# lizard-ttl-dLatch.net
KiCad netlist of a schematic drawn in EAGLE
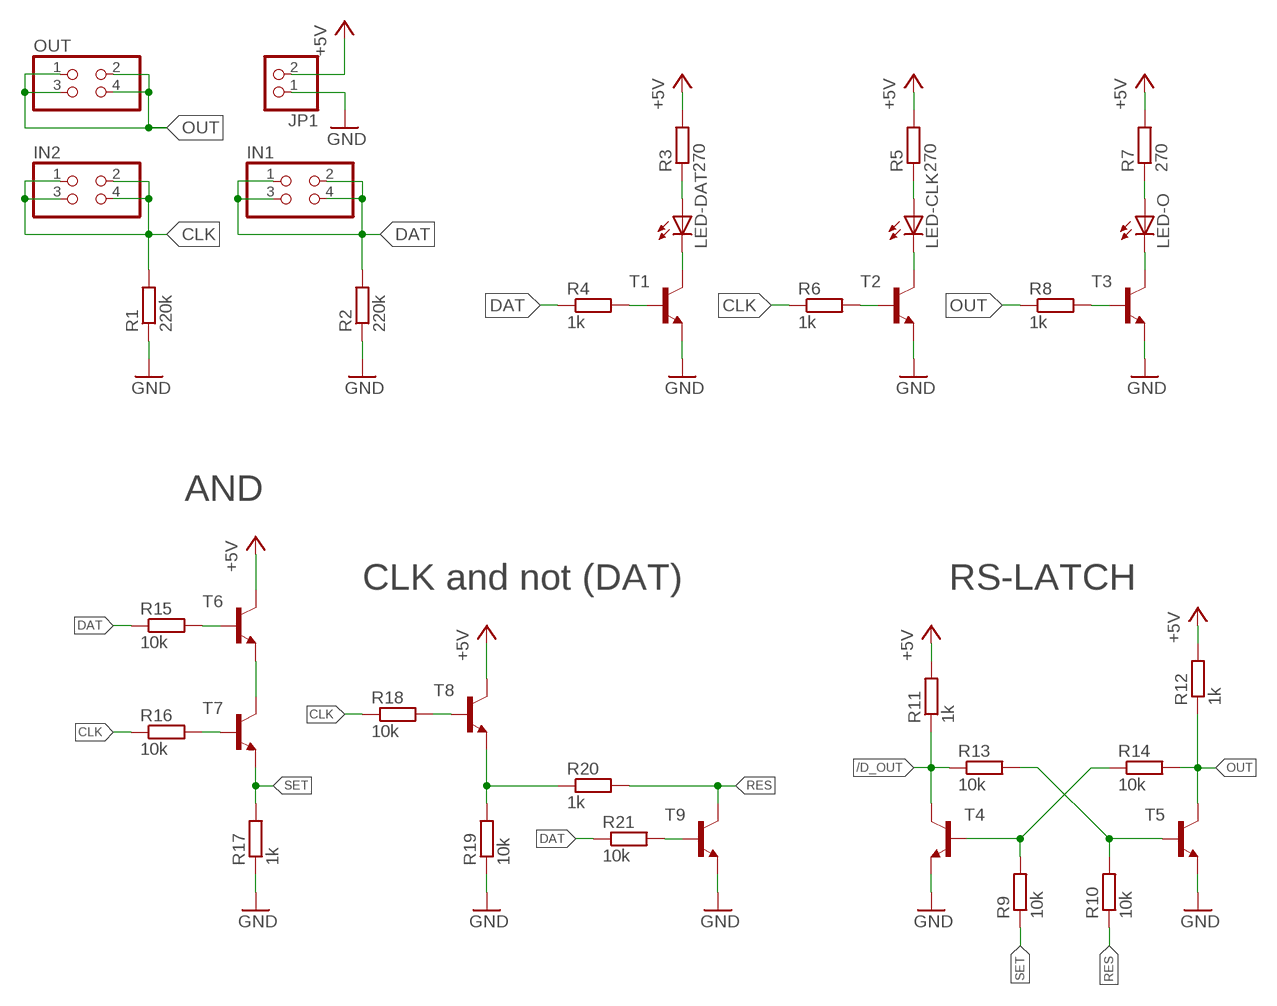
[diagram p0: schematic, sheet 1]

(export (version "E")
  (design (tool "Eeschema 10.0.6"))
  (components
    (comp (ref "IN1")
      (value "PINHD-2X2/EDGE")
      (footprint "eagle-import:2X02_EDGE")
      (libsource (lib "eagle-import") (part "PINHD-2X2/EDGE"))
    )
    (comp (ref "IN2")
      (value "PINHD-2X2/EDGE")
      (footprint "eagle-import:2X02_EDGE")
      (libsource (lib "eagle-import") (part "PINHD-2X2/EDGE"))
    )
    (comp (ref "JP1")
      (value "PINHD-1X2")
      (footprint "eagle-import:1X02")
      (libsource (lib "eagle-import") (part "PINHD-1X2"))
    )
    (comp (ref "LED-CLK")
      (value "LEDCHIPLED_0603")
      (footprint "eagle-import:CHIPLED_0603")
      (libsource (lib "eagle-import") (part "LEDCHIPLED_0603"))
    )
    (comp (ref "LED-DAT")
      (value "LEDCHIPLED_0603")
      (footprint "eagle-import:CHIPLED_0603")
      (libsource (lib "eagle-import") (part "LEDCHIPLED_0603"))
    )
    (comp (ref "LED-O")
      (value "LEDCHIPLED_0603")
      (footprint "eagle-import:CHIPLED_0603")
      (libsource (lib "eagle-import") (part "LEDCHIPLED_0603"))
    )
    (comp (ref "OUT")
      (value "PINHD-2X2/EDGE")
      (footprint "eagle-import:2X02_EDGE")
      (libsource (lib "eagle-import") (part "PINHD-2X2/EDGE"))
    )
    (comp (ref "R1")
      (value "220k")
      (footprint "eagle-import:R0603")
      (libsource (lib "eagle-import") (part "R-EU_R0603"))
    )
    (comp (ref "R2")
      (value "220k")
      (footprint "eagle-import:R0603")
      (libsource (lib "eagle-import") (part "R-EU_R0603"))
    )
    (comp (ref "R3")
      (value "270")
      (footprint "eagle-import:R0603")
      (libsource (lib "eagle-import") (part "R-EU_R0603"))
    )
    (comp (ref "R4")
      (value "1k")
      (footprint "eagle-import:R0603")
      (libsource (lib "eagle-import") (part "R-EU_R0603"))
    )
    (comp (ref "R5")
      (value "270")
      (footprint "eagle-import:R0603")
      (libsource (lib "eagle-import") (part "R-EU_R0603"))
    )
    (comp (ref "R6")
      (value "1k")
      (footprint "eagle-import:R0603")
      (libsource (lib "eagle-import") (part "R-EU_R0603"))
    )
    (comp (ref "R7")
      (value "270")
      (footprint "eagle-import:R0603")
      (libsource (lib "eagle-import") (part "R-EU_R0603"))
    )
    (comp (ref "R8")
      (value "1k")
      (footprint "eagle-import:R0603")
      (libsource (lib "eagle-import") (part "R-EU_R0603"))
    )
    (comp (ref "R9")
      (value "10k")
      (footprint "eagle-import:R0603")
      (libsource (lib "eagle-import") (part "R-EU_R0603"))
    )
    (comp (ref "R10")
      (value "10k")
      (footprint "eagle-import:R0603")
      (libsource (lib "eagle-import") (part "R-EU_R0603"))
    )
    (comp (ref "R11")
      (value "1k")
      (footprint "eagle-import:R0603")
      (libsource (lib "eagle-import") (part "R-EU_R0603"))
    )
    (comp (ref "R12")
      (value "1k")
      (footprint "eagle-import:R0603")
      (libsource (lib "eagle-import") (part "R-EU_R0603"))
    )
    (comp (ref "R13")
      (value "10k")
      (footprint "eagle-import:R0603")
      (libsource (lib "eagle-import") (part "R-EU_R0603"))
    )
    (comp (ref "R14")
      (value "10k")
      (footprint "eagle-import:R0603")
      (libsource (lib "eagle-import") (part "R-EU_R0603"))
    )
    (comp (ref "R15")
      (value "10k")
      (footprint "eagle-import:R0603")
      (libsource (lib "eagle-import") (part "R-EU_R0603"))
    )
    (comp (ref "R16")
      (value "10k")
      (footprint "eagle-import:R0603")
      (libsource (lib "eagle-import") (part "R-EU_R0603"))
    )
    (comp (ref "R17")
      (value "1k")
      (footprint "eagle-import:R0603")
      (libsource (lib "eagle-import") (part "R-EU_R0603"))
    )
    (comp (ref "R18")
      (value "10k")
      (footprint "eagle-import:R0603")
      (libsource (lib "eagle-import") (part "R-EU_R0603"))
    )
    (comp (ref "R19")
      (value "10k")
      (footprint "eagle-import:R0603")
      (libsource (lib "eagle-import") (part "R-EU_R0603"))
    )
    (comp (ref "R20")
      (value "1k")
      (footprint "eagle-import:R0603")
      (libsource (lib "eagle-import") (part "R-EU_R0603"))
    )
    (comp (ref "R21")
      (value "10k")
      (footprint "eagle-import:R0603")
      (libsource (lib "eagle-import") (part "R-EU_R0603"))
    )
    (comp (ref "T1")
      (value "BC817-40-NPN-SOT23-BEC")
      (footprint "eagle-import:SOT23-BEC")
      (libsource (lib "eagle-import") (part "-NPN-SOT23-BECBC817-40"))
    )
    (comp (ref "T2")
      (value "BC817-40-NPN-SOT23-BEC")
      (footprint "eagle-import:SOT23-BEC")
      (libsource (lib "eagle-import") (part "-NPN-SOT23-BECBC817-40"))
    )
    (comp (ref "T3")
      (value "BC817-40-NPN-SOT23-BEC")
      (footprint "eagle-import:SOT23-BEC")
      (libsource (lib "eagle-import") (part "-NPN-SOT23-BECBC817-40"))
    )
    (comp (ref "T4")
      (value "BC817-40-NPN-SOT23-BEC")
      (footprint "eagle-import:SOT23-BEC")
      (libsource (lib "eagle-import") (part "-NPN-SOT23-BECBC817-40"))
    )
    (comp (ref "T5")
      (value "BC817-40-NPN-SOT23-BEC")
      (footprint "eagle-import:SOT23-BEC")
      (libsource (lib "eagle-import") (part "-NPN-SOT23-BECBC817-40"))
    )
    (comp (ref "T6")
      (value "BC817-40-NPN-SOT23-BEC")
      (footprint "eagle-import:SOT23-BEC")
      (libsource (lib "eagle-import") (part "-NPN-SOT23-BECBC817-40"))
    )
    (comp (ref "T7")
      (value "BC817-40-NPN-SOT23-BEC")
      (footprint "eagle-import:SOT23-BEC")
      (libsource (lib "eagle-import") (part "-NPN-SOT23-BECBC817-40"))
    )
    (comp (ref "T8")
      (value "BC817-40-NPN-SOT23-BEC")
      (footprint "eagle-import:SOT23-BEC")
      (libsource (lib "eagle-import") (part "-NPN-SOT23-BECBC817-40"))
    )
    (comp (ref "T9")
      (value "BC817-40-NPN-SOT23-BEC")
      (footprint "eagle-import:SOT23-BEC")
      (libsource (lib "eagle-import") (part "-NPN-SOT23-BECBC817-40"))
    )
  )
  (nets
    (net (code "1") (name "+5V") (class "Default")
      (node (ref "JP1") (pin "2") (pinfunction "2_2") (pintype "passive"))
      (node (ref "R11") (pin "2") (pinfunction "2_2") (pintype "passive"))
      (node (ref "R12") (pin "2") (pinfunction "2_2") (pintype "passive"))
      (node (ref "R3") (pin "2") (pinfunction "2_2") (pintype "passive"))
      (node (ref "R5") (pin "2") (pinfunction "2_2") (pintype "passive"))
      (node (ref "R7") (pin "2") (pinfunction "2_2") (pintype "passive"))
      (node (ref "T6") (pin "C") (pinfunction "C_C") (pintype "passive"))
      (node (ref "T8") (pin "C") (pinfunction "C_C") (pintype "passive"))
    )
    (net (code "2") (name "CLK") (class "Default")
      (node (ref "IN2") (pin "1") (pinfunction "1_1") (pintype "passive"))
      (node (ref "IN2") (pin "2") (pinfunction "2_2") (pintype "passive"))
      (node (ref "IN2") (pin "3") (pinfunction "3_3") (pintype "passive"))
      (node (ref "IN2") (pin "4") (pinfunction "4_4") (pintype "passive"))
      (node (ref "R1") (pin "2") (pinfunction "2_2") (pintype "passive"))
      (node (ref "R16") (pin "1") (pinfunction "1_1") (pintype "passive"))
      (node (ref "R18") (pin "1") (pinfunction "1_1") (pintype "passive"))
      (node (ref "R6") (pin "1") (pinfunction "1_1") (pintype "passive"))
    )
    (net (code "3") (name "DAT") (class "Default")
      (node (ref "IN1") (pin "1") (pinfunction "1_1") (pintype "passive"))
      (node (ref "IN1") (pin "2") (pinfunction "2_2") (pintype "passive"))
      (node (ref "IN1") (pin "3") (pinfunction "3_3") (pintype "passive"))
      (node (ref "IN1") (pin "4") (pinfunction "4_4") (pintype "passive"))
      (node (ref "R15") (pin "1") (pinfunction "1_1") (pintype "passive"))
      (node (ref "R2") (pin "2") (pinfunction "2_2") (pintype "passive"))
      (node (ref "R21") (pin "1") (pinfunction "1_1") (pintype "passive"))
      (node (ref "R4") (pin "1") (pinfunction "1_1") (pintype "passive"))
    )
    (net (code "4") (name "GND") (class "Default")
      (node (ref "JP1") (pin "1") (pinfunction "1_1") (pintype "passive"))
      (node (ref "R1") (pin "1") (pinfunction "1_1") (pintype "passive"))
      (node (ref "R17") (pin "1") (pinfunction "1_1") (pintype "passive"))
      (node (ref "R19") (pin "1") (pinfunction "1_1") (pintype "passive"))
      (node (ref "R2") (pin "1") (pinfunction "1_1") (pintype "passive"))
      (node (ref "T1") (pin "E") (pinfunction "E_E") (pintype "passive"))
      (node (ref "T2") (pin "E") (pinfunction "E_E") (pintype "passive"))
      (node (ref "T3") (pin "E") (pinfunction "E_E") (pintype "passive"))
      (node (ref "T4") (pin "E") (pinfunction "E_E") (pintype "passive"))
      (node (ref "T5") (pin "E") (pinfunction "E_E") (pintype "passive"))
      (node (ref "T9") (pin "E") (pinfunction "E_E") (pintype "passive"))
    )
    (net (code "5") (name "Net-(LED-CLK-PadA)") (class "Default")
      (node (ref "LED-CLK") (pin "A") (pinfunction "A_A") (pintype "passive"))
      (node (ref "R5") (pin "1") (pinfunction "1_1") (pintype "passive"))
    )
    (net (code "6") (name "Net-(LED-CLK-PadC)") (class "Default")
      (node (ref "LED-CLK") (pin "C") (pinfunction "C_C") (pintype "passive"))
      (node (ref "T2") (pin "C") (pinfunction "C_C") (pintype "passive"))
    )
    (net (code "7") (name "Net-(LED-DAT-PadA)") (class "Default")
      (node (ref "LED-DAT") (pin "A") (pinfunction "A_A") (pintype "passive"))
      (node (ref "R3") (pin "1") (pinfunction "1_1") (pintype "passive"))
    )
    (net (code "8") (name "Net-(LED-DAT-PadC)") (class "Default")
      (node (ref "LED-DAT") (pin "C") (pinfunction "C_C") (pintype "passive"))
      (node (ref "T1") (pin "C") (pinfunction "C_C") (pintype "passive"))
    )
    (net (code "9") (name "Net-(LED-O-PadA)") (class "Default")
      (node (ref "LED-O") (pin "A") (pinfunction "A_A") (pintype "passive"))
      (node (ref "R7") (pin "1") (pinfunction "1_1") (pintype "passive"))
    )
    (net (code "10") (name "Net-(LED-O-PadC)") (class "Default")
      (node (ref "LED-O") (pin "C") (pinfunction "C_C") (pintype "passive"))
      (node (ref "T3") (pin "C") (pinfunction "C_C") (pintype "passive"))
    )
    (net (code "11") (name "Net-(R4-Pad2)") (class "Default")
      (node (ref "R4") (pin "2") (pinfunction "2_2") (pintype "passive"))
      (node (ref "T1") (pin "B") (pinfunction "B_B") (pintype "passive"))
    )
    (net (code "12") (name "Net-(R6-Pad2)") (class "Default")
      (node (ref "R6") (pin "2") (pinfunction "2_2") (pintype "passive"))
      (node (ref "T2") (pin "B") (pinfunction "B_B") (pintype "passive"))
    )
    (net (code "13") (name "Net-(R8-Pad2)") (class "Default")
      (node (ref "R8") (pin "2") (pinfunction "2_2") (pintype "passive"))
      (node (ref "T3") (pin "B") (pinfunction "B_B") (pintype "passive"))
    )
    (net (code "14") (name "Net-(R10-Pad2)") (class "Default")
      (node (ref "R10") (pin "2") (pinfunction "2_2") (pintype "passive"))
      (node (ref "R13") (pin "2") (pinfunction "2_2") (pintype "passive"))
      (node (ref "T5") (pin "B") (pinfunction "B_B") (pintype "passive"))
    )
    (net (code "15") (name "Net-(R14-Pad1)") (class "Default")
      (node (ref "R14") (pin "1") (pinfunction "1_1") (pintype "passive"))
      (node (ref "R9") (pin "2") (pinfunction "2_2") (pintype "passive"))
      (node (ref "T4") (pin "B") (pinfunction "B_B") (pintype "passive"))
    )
    (net (code "16") (name "Net-(R15-Pad2)") (class "Default")
      (node (ref "R15") (pin "2") (pinfunction "2_2") (pintype "passive"))
      (node (ref "T6") (pin "B") (pinfunction "B_B") (pintype "passive"))
    )
    (net (code "17") (name "Net-(R16-Pad2)") (class "Default")
      (node (ref "R16") (pin "2") (pinfunction "2_2") (pintype "passive"))
      (node (ref "T7") (pin "B") (pinfunction "B_B") (pintype "passive"))
    )
    (net (code "18") (name "Net-(R18-Pad2)") (class "Default")
      (node (ref "R18") (pin "2") (pinfunction "2_2") (pintype "passive"))
      (node (ref "T8") (pin "B") (pinfunction "B_B") (pintype "passive"))
    )
    (net (code "19") (name "Net-(R19-Pad2)") (class "Default")
      (node (ref "R19") (pin "2") (pinfunction "2_2") (pintype "passive"))
      (node (ref "R20") (pin "1") (pinfunction "1_1") (pintype "passive"))
      (node (ref "T8") (pin "E") (pinfunction "E_E") (pintype "passive"))
    )
    (net (code "20") (name "Net-(R21-Pad2)") (class "Default")
      (node (ref "R21") (pin "2") (pinfunction "2_2") (pintype "passive"))
      (node (ref "T9") (pin "B") (pinfunction "B_B") (pintype "passive"))
    )
    (net (code "21") (name "Net-(T6-PadE)") (class "Default")
      (node (ref "T6") (pin "E") (pinfunction "E_E") (pintype "passive"))
      (node (ref "T7") (pin "C") (pinfunction "C_C") (pintype "passive"))
    )
    (net (code "22") (name "OUT") (class "Default")
      (node (ref "OUT") (pin "1") (pinfunction "1_1") (pintype "passive"))
      (node (ref "OUT") (pin "2") (pinfunction "2_2") (pintype "passive"))
      (node (ref "OUT") (pin "3") (pinfunction "3_3") (pintype "passive"))
      (node (ref "OUT") (pin "4") (pinfunction "4_4") (pintype "passive"))
      (node (ref "R12") (pin "1") (pinfunction "1_1") (pintype "passive"))
      (node (ref "R14") (pin "2") (pinfunction "2_2") (pintype "passive"))
      (node (ref "R8") (pin "1") (pinfunction "1_1") (pintype "passive"))
      (node (ref "T5") (pin "C") (pinfunction "C_C") (pintype "passive"))
    )
    (net (code "23") (name "RES") (class "Default")
      (node (ref "R10") (pin "1") (pinfunction "1_1") (pintype "passive"))
      (node (ref "R20") (pin "2") (pinfunction "2_2") (pintype "passive"))
      (node (ref "T9") (pin "C") (pinfunction "C_C") (pintype "passive"))
    )
    (net (code "24") (name "SET") (class "Default")
      (node (ref "R17") (pin "2") (pinfunction "2_2") (pintype "passive"))
      (node (ref "R9") (pin "1") (pinfunction "1_1") (pintype "passive"))
      (node (ref "T7") (pin "E") (pinfunction "E_E") (pintype "passive"))
    )
    (net (code "25") (name "{slash}D_OUT") (class "Default")
      (node (ref "R11") (pin "1") (pinfunction "1_1") (pintype "passive"))
      (node (ref "R13") (pin "1") (pinfunction "1_1") (pintype "passive"))
      (node (ref "T4") (pin "C") (pinfunction "C_C") (pintype "passive"))
    )
  )
)
